# EFISSheet1.net
KiCad netlist of a schematic drawn in Altium Designer
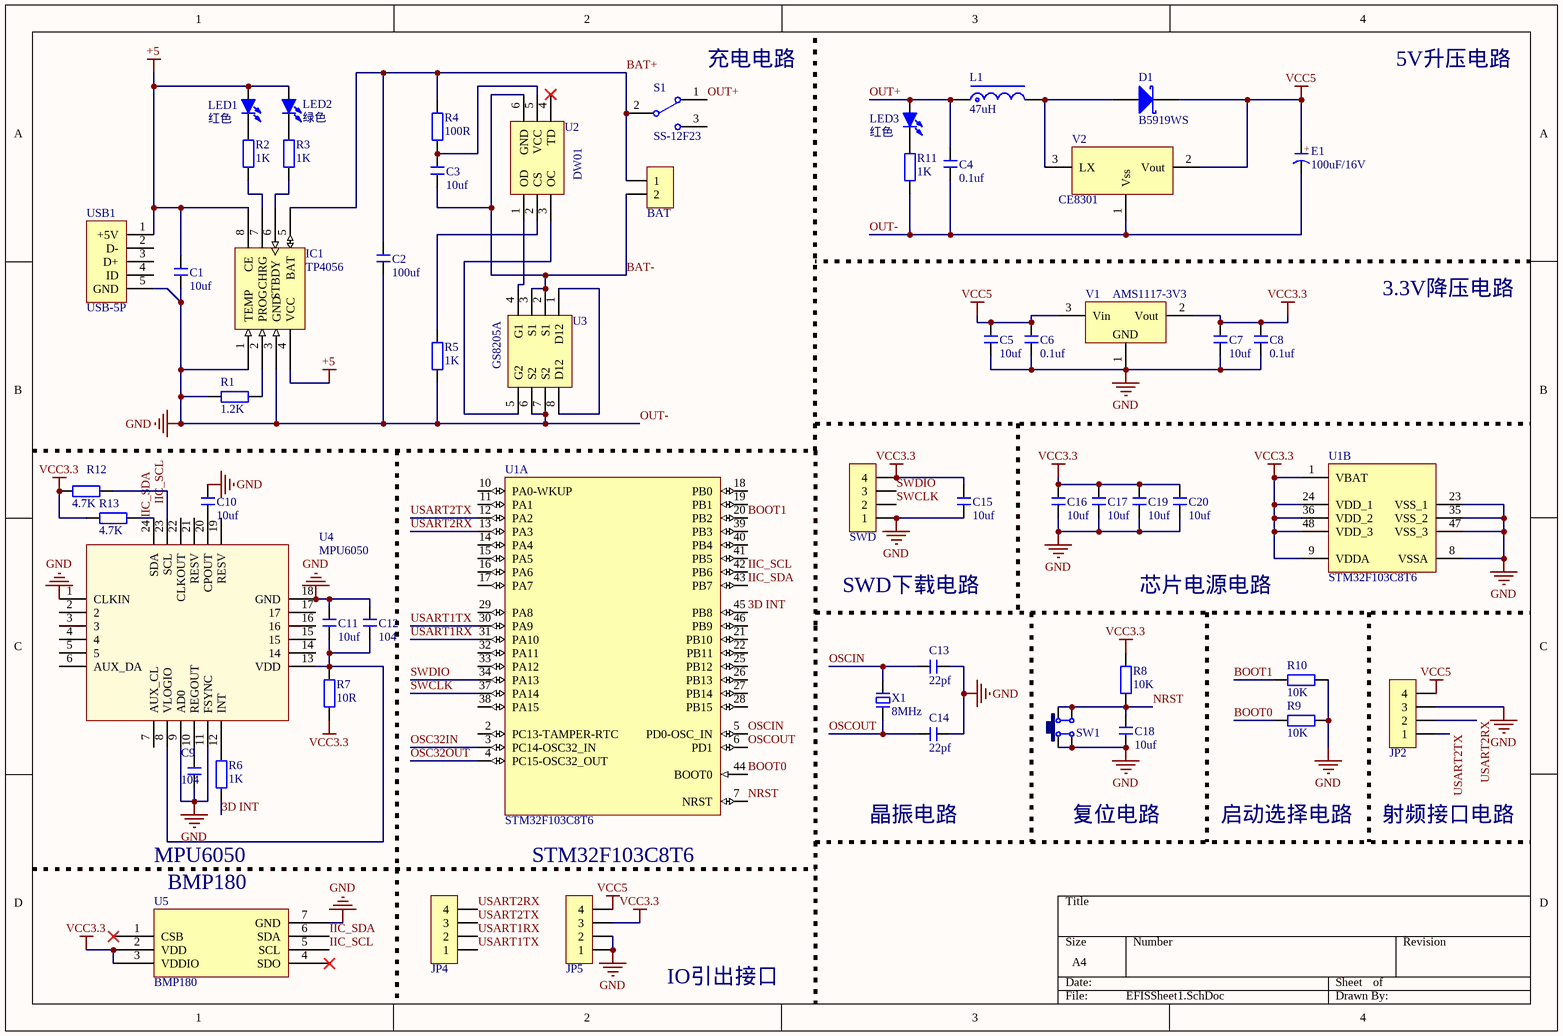
[diagram p0: EFISSheet1.SchDoc]

(export (version "E")
  (design (tool "Eeschema 10.0.6"))
  (components
    (comp (ref "BAT")
      (value "HDR-1X2")
      (footprint "XH2.54-LI-2P")
      (description "2P接插件")
      (fields (field (name "版权归属") "封装库来自淘宝 ID：黄晶宝石"))
      (libsource (lib "5.3 - 接插件-脚距2.54 (100mil) ") (part "Header 2"))
    )
    (comp (ref "C1")
      (value "10uf")
      (footprint "C 0805_L")
      (description "贴片电容")
      (libsource (lib "0.1 - 电阻-电容-电感") (part "C"))
    )
    (comp (ref "C2")
      (value "100uf")
      (footprint "C 0805_L")
      (description "贴片电容")
      (libsource (lib "0.1 - 电阻-电容-电感") (part "C"))
    )
    (comp (ref "C3")
      (value "10uf")
      (footprint "C 0805_L")
      (description "贴片电容")
      (libsource (lib "0.1 - 电阻-电容-电感") (part "C"))
    )
    (comp (ref "C4")
      (value "0.1uf")
      (footprint "C 0805_L")
      (description "贴片电容")
      (libsource (lib "0.1 - 电阻-电容-电感") (part "C"))
    )
    (comp (ref "C5")
      (value "10uf")
      (footprint "C 0805_L")
      (description "贴片电容")
      (libsource (lib "0.1 - 电阻-电容-电感") (part "C"))
    )
    (comp (ref "C6")
      (value "0.1uf")
      (footprint "C 0805_L")
      (description "贴片电容")
      (libsource (lib "0.1 - 电阻-电容-电感") (part "C"))
    )
    (comp (ref "C7")
      (value "10uf")
      (footprint "C 0805_L")
      (description "贴片电容")
      (libsource (lib "0.1 - 电阻-电容-电感") (part "C"))
    )
    (comp (ref "C8")
      (value "0.1uf")
      (footprint "C 0805_L")
      (description "贴片电容")
      (libsource (lib "0.1 - 电阻-电容-电感") (part "C"))
    )
    (comp (ref "C9")
      (value "104")
      (footprint "C 0805_L")
      (description "贴片电容")
      (libsource (lib "0.1 - 电阻-电容-电感") (part "C"))
    )
    (comp (ref "C10")
      (value "10uf")
      (footprint "C 0805_L")
      (description "贴片电容")
      (libsource (lib "0.1 - 电阻-电容-电感") (part "C"))
    )
    (comp (ref "C11")
      (value "10uf")
      (footprint "C 0805_L")
      (description "贴片电容")
      (libsource (lib "0.1 - 电阻-电容-电感") (part "C"))
    )
    (comp (ref "C12")
      (value "104")
      (footprint "C 0805_L")
      (description "贴片电容")
      (libsource (lib "0.1 - 电阻-电容-电感") (part "C"))
    )
    (comp (ref "C13")
      (value "22pf")
      (footprint "C 0805_L")
      (description "贴片电容")
      (libsource (lib "0.1 - 电阻-电容-电感") (part "C"))
    )
    (comp (ref "C14")
      (value "22pf")
      (footprint "C 0805_L")
      (description "贴片电容")
      (libsource (lib "0.1 - 电阻-电容-电感") (part "C"))
    )
    (comp (ref "C15")
      (value "10uf")
      (footprint "C 0805_L")
      (description "贴片电容")
      (libsource (lib "0.1 - 电阻-电容-电感") (part "C"))
    )
    (comp (ref "C16")
      (value "10uf")
      (footprint "C 0805_L")
      (description "贴片电容")
      (libsource (lib "0.1 - 电阻-电容-电感") (part "C"))
    )
    (comp (ref "C17")
      (value "10uf")
      (footprint "C 0805_L")
      (description "贴片电容")
      (libsource (lib "0.1 - 电阻-电容-电感") (part "C"))
    )
    (comp (ref "C18")
      (value "10uf")
      (footprint "C 0805_L")
      (description "贴片电容")
      (libsource (lib "0.1 - 电阻-电容-电感") (part "C"))
    )
    (comp (ref "C19")
      (value "10uf")
      (footprint "C 0805_L")
      (description "贴片电容")
      (libsource (lib "0.1 - 电阻-电容-电感") (part "C"))
    )
    (comp (ref "C20")
      (value "10uf")
      (footprint "C 0805_L")
      (description "贴片电容")
      (libsource (lib "0.1 - 电阻-电容-电感") (part "C"))
    )
    (comp (ref "D1")
      (value "B5919WS")
      (footprint "SOD-323")
      (description "肖特基二极管")
      (libsource (lib "0.2 -  二极管-整流桥") (part "1N5819"))
    )
    (comp (ref "E1")
      (value "100uF/16V")
      (footprint "CM D(6.3*5.4)")
      (description "贴片电解电容")
      (fields (field (name "版权归属") "封装库来自淘宝 ID：黄晶宝石"))
      (libsource (lib "0.1 - 电阻-电容-电感") (part "CE_SMD"))
    )
    (comp (ref "IC1")
      (value "TP4056")
      (footprint "SOP8_L")
      (description "外置EEPROM")
      (fields (field (name "版权归属") "封装库来自淘宝 ID：黄晶宝石"))
      (libsource (lib "1.0 - 常见芯片") (part "24Cxx"))
    )
    (comp (ref "JP2")
      (value "HDR-1X4")
      (footprint "HDR2.54-LI-4P")
      (description "4P接插件")
      (fields (field (name "版权归属") "封装库来自淘宝 ID：黄晶宝石"))
      (libsource (lib "5.3 - 接插件-脚距2.54 (100mil) ") (part "Header 4"))
    )
    (comp (ref "JP4")
      (value "HDR-1X4")
      (footprint "HDR2.54-LI-4P")
      (description "4P接插件")
      (fields (field (name "版权归属") "封装库来自淘宝 ID：黄晶宝石"))
      (libsource (lib "5.3 - 接插件-脚距2.54 (100mil) ") (part "Header 4"))
    )
    (comp (ref "JP5")
      (value "HDR-1X4")
      (footprint "HDR2.54-LI-4P")
      (description "4P接插件")
      (fields (field (name "版权归属") "封装库来自淘宝 ID：黄晶宝石"))
      (libsource (lib "5.3 - 接插件-脚距2.54 (100mil) ") (part "Header 4"))
    )
    (comp (ref "L1")
      (value "47uH")
      (footprint "CDRH73")
      (description "功率屏蔽电感")
      (fields (field (name "版权归属") "封装库来自淘宝 ID：黄晶宝石"))
      (libsource (lib "0.1 - 电阻-电容-电感") (part "L-CDRH"))
    )
    (comp (ref "LED1")
      (value "红色")
      (footprint "LED 0603R")
      (description "贴片LED")
      (fields (field (name "版权归属") "封装库来自淘宝 ID：黄晶宝石"))
      (libsource (lib "0.3 - LED发光二极管") (part "LED-SMD"))
    )
    (comp (ref "LED2")
      (value "绿色")
      (footprint "LED 0603G")
      (description "贴片LED")
      (fields (field (name "版权归属") "封装库来自淘宝 ID：黄晶宝石"))
      (libsource (lib "0.3 - LED发光二极管") (part "LED-SMD"))
    )
    (comp (ref "LED3")
      (value "红色")
      (footprint "LED 0603R")
      (description "贴片LED")
      (fields (field (name "版权归属") "封装库来自淘宝 ID：黄晶宝石"))
      (libsource (lib "0.3 - LED发光二极管") (part "LED-SMD"))
    )
    (comp (ref "R1")
      (value "1.2K")
      (footprint "R 0805_L")
      (description "贴片电阻")
      (fields (field (name "版权归属") "来自淘宝 ID：黄晶宝石"))
      (libsource (lib "0.1 - 电阻-电容-电感") (part "R"))
    )
    (comp (ref "R2")
      (value "1K")
      (footprint "R 0805_L")
      (description "贴片电阻")
      (fields (field (name "版权归属") "来自淘宝 ID：黄晶宝石"))
      (libsource (lib "0.1 - 电阻-电容-电感") (part "R"))
    )
    (comp (ref "R3")
      (value "1K")
      (footprint "R 0805_L")
      (description "贴片电阻")
      (fields (field (name "版权归属") "来自淘宝 ID：黄晶宝石"))
      (libsource (lib "0.1 - 电阻-电容-电感") (part "R"))
    )
    (comp (ref "R4")
      (value "100R")
      (footprint "R 0805_L")
      (description "贴片电阻")
      (fields (field (name "版权归属") "来自淘宝 ID：黄晶宝石"))
      (libsource (lib "0.1 - 电阻-电容-电感") (part "R"))
    )
    (comp (ref "R5")
      (value "1K")
      (footprint "R 0805_L")
      (description "贴片电阻")
      (fields (field (name "版权归属") "来自淘宝 ID：黄晶宝石"))
      (libsource (lib "0.1 - 电阻-电容-电感") (part "R"))
    )
    (comp (ref "R6")
      (value "1K")
      (footprint "R 0805_L")
      (description "贴片电阻")
      (fields (field (name "版权归属") "来自淘宝 ID：黄晶宝石"))
      (libsource (lib "0.1 - 电阻-电容-电感") (part "R"))
    )
    (comp (ref "R7")
      (value "10R")
      (footprint "R 0805_L")
      (description "贴片电阻")
      (fields (field (name "版权归属") "来自淘宝 ID：黄晶宝石"))
      (libsource (lib "0.1 - 电阻-电容-电感") (part "R"))
    )
    (comp (ref "R8")
      (value "10K")
      (footprint "R 0805_L")
      (description "贴片电阻")
      (fields (field (name "版权归属") "来自淘宝 ID：黄晶宝石"))
      (libsource (lib "0.1 - 电阻-电容-电感") (part "R"))
    )
    (comp (ref "R9")
      (value "10K")
      (footprint "R 0805_L")
      (description "贴片电阻")
      (fields (field (name "版权归属") "来自淘宝 ID：黄晶宝石"))
      (libsource (lib "0.1 - 电阻-电容-电感") (part "R"))
    )
    (comp (ref "R10")
      (value "10K")
      (footprint "R 0805_L")
      (description "贴片电阻")
      (fields (field (name "版权归属") "来自淘宝 ID：黄晶宝石"))
      (libsource (lib "0.1 - 电阻-电容-电感") (part "R"))
    )
    (comp (ref "R11")
      (value "1K")
      (footprint "R 0805_L")
      (description "贴片电阻")
      (fields (field (name "版权归属") "来自淘宝 ID：黄晶宝石"))
      (libsource (lib "0.1 - 电阻-电容-电感") (part "R"))
    )
    (comp (ref "R12")
      (value "4.7K")
      (footprint "R 0805_L")
      (description "贴片电阻")
      (fields (field (name "版权归属") "来自淘宝 ID：黄晶宝石"))
      (libsource (lib "0.1 - 电阻-电容-电感") (part "R"))
    )
    (comp (ref "R13")
      (value "4.7K")
      (footprint "R 0805_L")
      (description "贴片电阻")
      (fields (field (name "版权归属") "来自淘宝 ID：黄晶宝石"))
      (libsource (lib "0.1 - 电阻-电容-电感") (part "R"))
    )
    (comp (ref "S1")
      (value "SS-12F23")
      (footprint "MSK-12C01-07")
      (description "1路波动开关")
      (fields (field (name "版权归属") "封装库来自淘宝 ID：黄晶宝石"))
      (libsource (lib "0.7 - 常用按键-开关") (part "SSW-1P"))
    )
    (comp (ref "SW1")
      (value "6x6x5")
      (footprint "TSW SMD-6*6*5")
      (description "贴片6x6轻触开关")
      (fields (field (name "版权归属") "封装库来自淘宝 ID：黄晶宝石"))
      (libsource (lib "0.7 - 常用按键-开关") (part "TSW SMD-6x6"))
    )
    (comp (ref "SWD")
      (value "HDR-1X4")
      (footprint "HDR2.54-LI-4P")
      (description "4P接插件")
      (fields (field (name "版权归属") "封装库来自淘宝 ID：黄晶宝石"))
      (libsource (lib "5.3 - 接插件-脚距2.54 (100mil) ") (part "Header 4"))
    )
    (comp (ref "U1")
      (value "STM32F103C8T6")
      (footprint "LQFP48_N")
      (libsource (lib "2.3 - STM32 F1系列MCU 集成库") (part "STM32F103C8T6"))
    )
    (comp (ref "U2")
      (value "DW01")
      (footprint "SOT23-6N")
      (description "锂电池过流保护IC")
      (libsource (lib "1.1 - 电源类芯片") (part "DW01"))
    )
    (comp (ref "U3")
      (value "GS8205A")
      (footprint "SSOP8_N")
      (description "N沟道增强型功率场效应管")
      (fields (field (name "版权归属") "源创客"))
      (libsource (lib "0.5 - 场效应管-可控硅") (part "GS8205A"))
    )
    (comp (ref "U4")
      (value "MPU6050")
      (footprint "QFN_24")
      (description "三轴加速度+三轴陀螺仪")
      (libsource (lib "1.0 - 常见芯片") (part "MPU6050"))
    )
    (comp (ref "U5") (value "BMP180") (footprint "LGA7") (libsource (lib "Schlib1") (part "BMP180")))
    (comp (ref "USB1")
      (value "USB-5P")
      (footprint "USB-MICRO_A")
      (description "微型USB母座")
      (libsource (lib "0.8 - 以太网-音频-USB插座") (part "USB-5P"))
    )
    (comp (ref "V1")
      (value "AMS1117-3V3")
      (footprint "SOT223_N")
      (description "三端稳压芯片")
      (libsource (lib "1.1 - 电源类芯片") (part "AMS1117"))
    )
    (comp (ref "V2")
      (value "CE8301")
      (footprint "SOT89_N")
      (description "LDO线性稳压芯片")
      (fields (field (name "版权归属") "封装库来自淘宝 ID：黄晶宝石"))
      (libsource (lib "1.1 - 电源类芯片") (part "HT71xx"))
    )
    (comp (ref "X1")
      (value "8MHz")
      (footprint "OSC HC-49SMD")
      (description "2脚无源脚晶振")
      (fields (field (name "版权归属") "封装库来自淘宝卖家 ID：黄晶宝石"))
      (libsource (lib "2.0 - 保险丝-晶振-光耦") (part "XTAL-2P"))
    )
  )
  (nets
    (net (code "1") (name "+5") (class "Default")
      (node (ref "C1") (pin "2") (pinfunction "2_2") (pintype "passive"))
      (node (ref "IC1") (pin "4") (pinfunction "VCC_4") (pintype "passive"))
      (node (ref "IC1") (pin "8") (pinfunction "CE_8") (pintype "power_in"))
      (node (ref "LED1") (pin "1") (pinfunction "A_1") (pintype "passive"))
      (node (ref "LED2") (pin "1") (pinfunction "A_1") (pintype "passive"))
      (node (ref "USB1") (pin "1") (pinfunction "+5V_1") (pintype "passive"))
    )
    (net (code "2") (name "/3D INT") (class "Default")
      (node (ref "R6") (pin "2") (pinfunction "2_2") (pintype "passive"))
      (node (ref "U1") (pin "45") (pinfunction "PB8_45") (pintype "bidirectional"))
    )
    (net (code "3") (name "/BAT+") (class "Default")
      (node (ref "BAT") (pin "1") (pinfunction "1_1") (pintype "passive"))
      (node (ref "C2") (pin "2") (pinfunction "2_2") (pintype "passive"))
      (node (ref "IC1") (pin "5") (pinfunction "BAT_5") (pintype "bidirectional"))
      (node (ref "R4") (pin "2") (pinfunction "2_2") (pintype "passive"))
      (node (ref "S1") (pin "2") (pinfunction "2_2") (pintype "passive"))
    )
    (net (code "4") (name "/BAT-") (class "Default")
      (node (ref "BAT") (pin "2") (pinfunction "2_2") (pintype "passive"))
      (node (ref "C3") (pin "1") (pinfunction "1_1") (pintype "passive"))
      (node (ref "U2") (pin "6") (pinfunction "GND_6") (pintype "passive"))
      (node (ref "U3") (pin "2") (pinfunction "S1_2") (pintype "passive"))
      (node (ref "U3") (pin "3") (pinfunction "S1_3") (pintype "passive"))
    )
    (net (code "5") (name "/BOOT0") (class "Default")
      (node (ref "R9") (pin "2") (pinfunction "2_2") (pintype "passive"))
      (node (ref "U1") (pin "44") (pinfunction "BOOT0_44") (pintype "input"))
    )
    (net (code "6") (name "/BOOT1") (class "Default")
      (node (ref "R10") (pin "1") (pinfunction "1_1") (pintype "passive"))
      (node (ref "U1") (pin "20") (pinfunction "PB2_20") (pintype "bidirectional"))
    )
    (net (code "7") (name "/IIC_SCL") (class "Default")
      (node (ref "R12") (pin "2") (pinfunction "2_2") (pintype "passive"))
      (node (ref "U1") (pin "42") (pinfunction "PB6_42") (pintype "bidirectional"))
      (node (ref "U4") (pin "23") (pinfunction "SCL_23") (pintype "passive"))
      (node (ref "U5") (pin "5") (pinfunction "SCL_5") (pintype "passive"))
    )
    (net (code "8") (name "/IIC_SDA") (class "Default")
      (node (ref "R13") (pin "2") (pinfunction "2_2") (pintype "passive"))
      (node (ref "U1") (pin "43") (pinfunction "PB7_43") (pintype "bidirectional"))
      (node (ref "U4") (pin "24") (pinfunction "SDA_24") (pintype "passive"))
      (node (ref "U5") (pin "6") (pinfunction "SDA_6") (pintype "passive"))
    )
    (net (code "9") (name "/NRST") (class "Default")
      (node (ref "C18") (pin "2") (pinfunction "2_2") (pintype "passive"))
      (node (ref "R8") (pin "2") (pinfunction "2_2") (pintype "passive"))
      (node (ref "SW1") (pin "2") (pinfunction "2_2") (pintype "passive"))
      (node (ref "SW1") (pin "3") (pinfunction "3_3") (pintype "passive"))
      (node (ref "U1") (pin "7") (pinfunction "NRST_7") (pintype "bidirectional"))
    )
    (net (code "10") (name "/OSC32IN") (class "Default")
      (node (ref "U1") (pin "3") (pinfunction "PC14-OSC32_IN_3") (pintype "bidirectional"))
    )
    (net (code "11") (name "/OSC32OUT") (class "Default")
      (node (ref "U1") (pin "4") (pinfunction "PC15-OSC32_OUT_4") (pintype "bidirectional"))
    )
    (net (code "12") (name "/OSCIN") (class "Default")
      (node (ref "C13") (pin "2") (pinfunction "2_2") (pintype "passive"))
      (node (ref "U1") (pin "5") (pinfunction "PD0-OSC_IN_5") (pintype "bidirectional"))
      (node (ref "X1") (pin "2") (pinfunction "2_2") (pintype "passive"))
    )
    (net (code "13") (name "/OSCOUT") (class "Default")
      (node (ref "C14") (pin "2") (pinfunction "2_2") (pintype "passive"))
      (node (ref "U1") (pin "6") (pinfunction "PD1_6") (pintype "bidirectional"))
      (node (ref "X1") (pin "1") (pinfunction "1_1") (pintype "passive"))
    )
    (net (code "14") (name "/OUT+") (class "Default")
      (node (ref "C4") (pin "2") (pinfunction "2_2") (pintype "passive"))
      (node (ref "L1") (pin "1") (pinfunction "1_1") (pintype "passive"))
      (node (ref "LED3") (pin "1") (pinfunction "A_1") (pintype "passive"))
      (node (ref "S1") (pin "1") (pinfunction "1_1") (pintype "passive"))
    )
    (net (code "15") (name "/SWCLK") (class "Default")
      (node (ref "SWD") (pin "2") (pinfunction "2_2") (pintype "passive"))
      (node (ref "U1") (pin "37") (pinfunction "PA14_37") (pintype "bidirectional"))
    )
    (net (code "16") (name "/SWDIO") (class "Default")
      (node (ref "SWD") (pin "3") (pinfunction "3_3") (pintype "passive"))
      (node (ref "U1") (pin "34") (pinfunction "PA13_34") (pintype "bidirectional"))
    )
    (net (code "17") (name "/USART1RX") (class "Default")
      (node (ref "JP4") (pin "2") (pinfunction "2_2") (pintype "passive"))
      (node (ref "U1") (pin "31") (pinfunction "PA10_31") (pintype "bidirectional"))
    )
    (net (code "18") (name "/USART1TX") (class "Default")
      (node (ref "JP4") (pin "1") (pinfunction "1_1") (pintype "passive"))
      (node (ref "U1") (pin "30") (pinfunction "PA9_30") (pintype "bidirectional"))
    )
    (net (code "19") (name "/USART2RX") (class "Default")
      (node (ref "JP2") (pin "2") (pinfunction "2_2") (pintype "passive"))
      (node (ref "JP4") (pin "4") (pinfunction "4_4") (pintype "passive"))
      (node (ref "U1") (pin "13") (pinfunction "PA3_13") (pintype "bidirectional"))
    )
    (net (code "20") (name "/USART2TX") (class "Default")
      (node (ref "JP2") (pin "1") (pinfunction "1_1") (pintype "passive"))
      (node (ref "JP4") (pin "3") (pinfunction "3_3") (pintype "passive"))
      (node (ref "U1") (pin "12") (pinfunction "PA2_12") (pintype "bidirectional"))
    )
    (net (code "21") (name "GND") (class "Default")
      (node (ref "C1") (pin "1") (pinfunction "1_1") (pintype "passive"))
      (node (ref "C10") (pin "2") (pinfunction "2_2") (pintype "passive"))
      (node (ref "C11") (pin "2") (pinfunction "2_2") (pintype "passive"))
      (node (ref "C12") (pin "2") (pinfunction "2_2") (pintype "passive"))
      (node (ref "C13") (pin "1") (pinfunction "1_1") (pintype "passive"))
      (node (ref "C14") (pin "1") (pinfunction "1_1") (pintype "passive"))
      (node (ref "C15") (pin "1") (pinfunction "1_1") (pintype "passive"))
      (node (ref "C16") (pin "1") (pinfunction "1_1") (pintype "passive"))
      (node (ref "C17") (pin "1") (pinfunction "1_1") (pintype "passive"))
      (node (ref "C18") (pin "1") (pinfunction "1_1") (pintype "passive"))
      (node (ref "C19") (pin "1") (pinfunction "1_1") (pintype "passive"))
      (node (ref "C2") (pin "1") (pinfunction "1_1") (pintype "passive"))
      (node (ref "C20") (pin "1") (pinfunction "1_1") (pintype "passive"))
      (node (ref "C4") (pin "1") (pinfunction "1_1") (pintype "passive"))
      (node (ref "C5") (pin "1") (pinfunction "1_1") (pintype "passive"))
      (node (ref "C6") (pin "1") (pinfunction "1_1") (pintype "passive"))
      (node (ref "C7") (pin "1") (pinfunction "1_1") (pintype "passive"))
      (node (ref "C8") (pin "1") (pinfunction "1_1") (pintype "passive"))
      (node (ref "C9") (pin "1") (pinfunction "1_1") (pintype "passive"))
      (node (ref "E1") (pin "2") (pinfunction "K_2") (pintype "passive"))
      (node (ref "IC1") (pin "1") (pinfunction "TEMP_1") (pintype "input"))
      (node (ref "IC1") (pin "3") (pinfunction "GND_3") (pintype "input"))
      (node (ref "JP2") (pin "3") (pinfunction "3_3") (pintype "passive"))
      (node (ref "JP5") (pin "1") (pinfunction "1_1") (pintype "passive"))
      (node (ref "JP5") (pin "2") (pinfunction "2_2") (pintype "passive"))
      (node (ref "R1") (pin "1") (pinfunction "1_1") (pintype "passive"))
      (node (ref "R10") (pin "2") (pinfunction "2_2") (pintype "passive"))
      (node (ref "R11") (pin "2") (pinfunction "2_2") (pintype "passive"))
      (node (ref "R5") (pin "1") (pinfunction "1_1") (pintype "passive"))
      (node (ref "R9") (pin "1") (pinfunction "1_1") (pintype "passive"))
      (node (ref "SW1") (pin "1") (pinfunction "1_1") (pintype "passive"))
      (node (ref "SW1") (pin "4") (pinfunction "4_4") (pintype "passive"))
      (node (ref "SWD") (pin "1") (pinfunction "1_1") (pintype "passive"))
      (node (ref "U1") (pin "23") (pinfunction "VSS_1_23") (pintype "power_in"))
      (node (ref "U1") (pin "35") (pinfunction "VSS_2_35") (pintype "power_in"))
      (node (ref "U1") (pin "47") (pinfunction "VSS_3_47") (pintype "power_in"))
      (node (ref "U1") (pin "8") (pinfunction "VSSA_8") (pintype "power_in"))
      (node (ref "U3") (pin "6") (pinfunction "S2_6") (pintype "passive"))
      (node (ref "U3") (pin "7") (pinfunction "S2_7") (pintype "passive"))
      (node (ref "U4") (pin "1") (pinfunction "CLKIN_1") (pintype "passive"))
      (node (ref "U4") (pin "11") (pinfunction "FSYNC_11") (pintype "passive"))
      (node (ref "U4") (pin "18") (pinfunction "GND_18") (pintype "passive"))
      (node (ref "U4") (pin "9") (pinfunction "AD0_9") (pintype "passive"))
      (node (ref "U5") (pin "7") (pinfunction "GND_7") (pintype "passive"))
      (node (ref "USB1") (pin "5") (pinfunction "GND_5") (pintype "passive"))
      (node (ref "V1") (pin "1") (pinfunction "GND_1") (pintype "passive"))
      (node (ref "V2") (pin "1") (pinfunction "Vss_1") (pintype "passive"))
    )
    (net (code "22") (name "Net-(D1-A)") (class "Default")
      (node (ref "D1") (pin "1") (pinfunction "A_1") (pintype "passive"))
      (node (ref "L1") (pin "2") (pinfunction "2_2") (pintype "passive"))
      (node (ref "V2") (pin "3") (pinfunction "LX_3") (pintype "passive"))
    )
    (net (code "23") (name "Net-(IC1-CHRG)") (class "Default")
      (node (ref "IC1") (pin "7") (pinfunction "CHRG_7") (pintype "passive"))
      (node (ref "R2") (pin "2") (pinfunction "2_2") (pintype "passive"))
    )
    (net (code "24") (name "Net-(IC1-PROG)") (class "Default")
      (node (ref "IC1") (pin "2") (pinfunction "PROG_2") (pintype "input"))
      (node (ref "R1") (pin "2") (pinfunction "2_2") (pintype "passive"))
    )
    (net (code "25") (name "Net-(IC1-STBDY)") (class "Default")
      (node (ref "IC1") (pin "6") (pinfunction "STBDY_6") (pintype "input"))
      (node (ref "R3") (pin "1") (pinfunction "1_1") (pintype "passive"))
    )
    (net (code "26") (name "Net-(LED1-K)") (class "Default")
      (node (ref "LED1") (pin "2") (pinfunction "K_2") (pintype "passive"))
      (node (ref "R2") (pin "1") (pinfunction "1_1") (pintype "passive"))
    )
    (net (code "27") (name "Net-(LED2-K)") (class "Default")
      (node (ref "LED2") (pin "2") (pinfunction "K_2") (pintype "passive"))
      (node (ref "R3") (pin "2") (pinfunction "2_2") (pintype "passive"))
    )
    (net (code "28") (name "Net-(LED3-K)") (class "Default")
      (node (ref "LED3") (pin "2") (pinfunction "K_2") (pintype "passive"))
      (node (ref "R11") (pin "1") (pinfunction "1_1") (pintype "passive"))
    )
    (net (code "29") (name "Net-(U2-CS)") (class "Default")
      (node (ref "R5") (pin "2") (pinfunction "2_2") (pintype "passive"))
      (node (ref "U2") (pin "2") (pinfunction "CS_2") (pintype "passive"))
    )
    (net (code "30") (name "Net-(U2-OC)") (class "Default")
      (node (ref "U2") (pin "3") (pinfunction "OC_3") (pintype "passive"))
      (node (ref "U3") (pin "5") (pinfunction "G2_5") (pintype "passive"))
    )
    (net (code "31") (name "Net-(U2-OD)") (class "Default")
      (node (ref "U2") (pin "1") (pinfunction "OD_1") (pintype "passive"))
      (node (ref "U3") (pin "4") (pinfunction "G1_4") (pintype "passive"))
    )
    (net (code "32") (name "Net-(U2-VCC)") (class "Default")
      (node (ref "C3") (pin "2") (pinfunction "2_2") (pintype "passive"))
      (node (ref "R4") (pin "1") (pinfunction "1_1") (pintype "passive"))
      (node (ref "U2") (pin "5") (pinfunction "VCC_5") (pintype "passive"))
    )
    (net (code "33") (name "Net-(U3-D12-Pad1)") (class "Default")
      (node (ref "U3") (pin "1") (pinfunction "D12_1") (pintype "passive"))
      (node (ref "U3") (pin "8") (pinfunction "D12_8") (pintype "passive"))
    )
    (net (code "34") (name "Net-(U4-CPOUT)") (class "Default")
      (node (ref "C10") (pin "1") (pinfunction "1_1") (pintype "passive"))
      (node (ref "U4") (pin "20") (pinfunction "CPOUT_20") (pintype "passive"))
    )
    (net (code "35") (name "Net-(U4-INT)") (class "Default")
      (node (ref "R6") (pin "1") (pinfunction "1_1") (pintype "passive"))
      (node (ref "U4") (pin "12") (pinfunction "INT_12") (pintype "passive"))
    )
    (net (code "36") (name "Net-(U4-REGOUT)") (class "Default")
      (node (ref "C9") (pin "2") (pinfunction "2_2") (pintype "passive"))
      (node (ref "U4") (pin "10") (pinfunction "REGOUT_10") (pintype "passive"))
    )
    (net (code "37") (name "Net-(U4-VDD)") (class "Default")
      (node (ref "C11") (pin "1") (pinfunction "1_1") (pintype "passive"))
      (node (ref "C12") (pin "1") (pinfunction "1_1") (pintype "passive"))
      (node (ref "R7") (pin "2") (pinfunction "2_2") (pintype "passive"))
      (node (ref "U4") (pin "13") (pinfunction "VDD_13") (pintype "passive"))
      (node (ref "U4") (pin "8") (pinfunction "VLOGIO_8") (pintype "passive"))
    )
    (net (code "38") (name "VCC3.3") (class "Default")
      (node (ref "C15") (pin "2") (pinfunction "2_2") (pintype "passive"))
      (node (ref "C16") (pin "2") (pinfunction "2_2") (pintype "passive"))
      (node (ref "C17") (pin "2") (pinfunction "2_2") (pintype "passive"))
      (node (ref "C19") (pin "2") (pinfunction "2_2") (pintype "passive"))
      (node (ref "C20") (pin "2") (pinfunction "2_2") (pintype "passive"))
      (node (ref "C7") (pin "2") (pinfunction "2_2") (pintype "passive"))
      (node (ref "C8") (pin "2") (pinfunction "2_2") (pintype "passive"))
      (node (ref "JP5") (pin "3") (pinfunction "3_3") (pintype "passive"))
      (node (ref "R12") (pin "1") (pinfunction "1_1") (pintype "passive"))
      (node (ref "R13") (pin "1") (pinfunction "1_1") (pintype "passive"))
      (node (ref "R7") (pin "1") (pinfunction "1_1") (pintype "passive"))
      (node (ref "R8") (pin "1") (pinfunction "1_1") (pintype "passive"))
      (node (ref "SWD") (pin "4") (pinfunction "4_4") (pintype "passive"))
      (node (ref "U1") (pin "1") (pinfunction "VBAT_1") (pintype "power_in"))
      (node (ref "U1") (pin "24") (pinfunction "VDD_1_24") (pintype "power_in"))
      (node (ref "U1") (pin "36") (pinfunction "VDD_2_36") (pintype "power_in"))
      (node (ref "U1") (pin "48") (pinfunction "VDD_3_48") (pintype "power_in"))
      (node (ref "U1") (pin "9") (pinfunction "VDDA_9") (pintype "power_in"))
      (node (ref "U5") (pin "2") (pinfunction "VDD_2") (pintype "passive"))
      (node (ref "U5") (pin "3") (pinfunction "VDDIO_3") (pintype "passive"))
      (node (ref "V1") (pin "2") (pinfunction "Vout_2") (pintype "passive"))
    )
    (net (code "39") (name "VCC5") (class "Default")
      (node (ref "C5") (pin "2") (pinfunction "2_2") (pintype "passive"))
      (node (ref "C6") (pin "2") (pinfunction "2_2") (pintype "passive"))
      (node (ref "D1") (pin "2") (pinfunction "K_2") (pintype "passive"))
      (node (ref "E1") (pin "1") (pinfunction "A_1") (pintype "passive"))
      (node (ref "JP2") (pin "4") (pinfunction "4_4") (pintype "passive"))
      (node (ref "JP5") (pin "4") (pinfunction "4_4") (pintype "passive"))
      (node (ref "V1") (pin "3") (pinfunction "Vin_3") (pintype "passive"))
      (node (ref "V2") (pin "2") (pinfunction "Vout_2") (pintype "passive"))
    )
    (net (code "40") (name "unconnected-(S1-Pad3)") (class "Default")
      (node (ref "S1") (pin "3") (pinfunction "3_3") (pintype "passive"))
    )
    (net (code "41") (name "unconnected-(U1A-PA0-WKUP-Pad10)") (class "Default")
      (node (ref "U1") (pin "10") (pinfunction "PA0-WKUP_10") (pintype "bidirectional"))
    )
    (net (code "42") (name "unconnected-(U1A-PA1-Pad11)") (class "Default")
      (node (ref "U1") (pin "11") (pinfunction "PA1_11") (pintype "bidirectional"))
    )
    (net (code "43") (name "unconnected-(U1A-PA4-Pad14)") (class "Default")
      (node (ref "U1") (pin "14") (pinfunction "PA4_14") (pintype "bidirectional"))
    )
    (net (code "44") (name "unconnected-(U1A-PA5-Pad15)") (class "Default")
      (node (ref "U1") (pin "15") (pinfunction "PA5_15") (pintype "bidirectional"))
    )
    (net (code "45") (name "unconnected-(U1A-PA6-Pad16)") (class "Default")
      (node (ref "U1") (pin "16") (pinfunction "PA6_16") (pintype "bidirectional"))
    )
    (net (code "46") (name "unconnected-(U1A-PA7-Pad17)") (class "Default")
      (node (ref "U1") (pin "17") (pinfunction "PA7_17") (pintype "bidirectional"))
    )
    (net (code "47") (name "unconnected-(U1A-PA8-Pad29)") (class "Default")
      (node (ref "U1") (pin "29") (pinfunction "PA8_29") (pintype "bidirectional"))
    )
    (net (code "48") (name "unconnected-(U1A-PA11-Pad32)") (class "Default")
      (node (ref "U1") (pin "32") (pinfunction "PA11_32") (pintype "bidirectional"))
    )
    (net (code "49") (name "unconnected-(U1A-PA12-Pad33)") (class "Default")
      (node (ref "U1") (pin "33") (pinfunction "PA12_33") (pintype "bidirectional"))
    )
    (net (code "50") (name "unconnected-(U1A-PA15-Pad38)") (class "Default")
      (node (ref "U1") (pin "38") (pinfunction "PA15_38") (pintype "bidirectional"))
    )
    (net (code "51") (name "unconnected-(U1A-PB0-Pad18)") (class "Default")
      (node (ref "U1") (pin "18") (pinfunction "PB0_18") (pintype "bidirectional"))
    )
    (net (code "52") (name "unconnected-(U1A-PB1-Pad19)") (class "Default")
      (node (ref "U1") (pin "19") (pinfunction "PB1_19") (pintype "bidirectional"))
    )
    (net (code "53") (name "unconnected-(U1A-PB3-Pad39)") (class "Default")
      (node (ref "U1") (pin "39") (pinfunction "PB3_39") (pintype "bidirectional"))
    )
    (net (code "54") (name "unconnected-(U1A-PB4-Pad40)") (class "Default")
      (node (ref "U1") (pin "40") (pinfunction "PB4_40") (pintype "bidirectional"))
    )
    (net (code "55") (name "unconnected-(U1A-PB5-Pad41)") (class "Default")
      (node (ref "U1") (pin "41") (pinfunction "PB5_41") (pintype "bidirectional"))
    )
    (net (code "56") (name "unconnected-(U1A-PB9-Pad46)") (class "Default")
      (node (ref "U1") (pin "46") (pinfunction "PB9_46") (pintype "bidirectional"))
    )
    (net (code "57") (name "unconnected-(U1A-PB10-Pad21)") (class "Default")
      (node (ref "U1") (pin "21") (pinfunction "PB10_21") (pintype "bidirectional"))
    )
    (net (code "58") (name "unconnected-(U1A-PB11-Pad22)") (class "Default")
      (node (ref "U1") (pin "22") (pinfunction "PB11_22") (pintype "bidirectional"))
    )
    (net (code "59") (name "unconnected-(U1A-PB12-Pad25)") (class "Default")
      (node (ref "U1") (pin "25") (pinfunction "PB12_25") (pintype "bidirectional"))
    )
    (net (code "60") (name "unconnected-(U1A-PB13-Pad26)") (class "Default")
      (node (ref "U1") (pin "26") (pinfunction "PB13_26") (pintype "bidirectional"))
    )
    (net (code "61") (name "unconnected-(U1A-PB14-Pad27)") (class "Default")
      (node (ref "U1") (pin "27") (pinfunction "PB14_27") (pintype "bidirectional"))
    )
    (net (code "62") (name "unconnected-(U1A-PB15-Pad28)") (class "Default")
      (node (ref "U1") (pin "28") (pinfunction "PB15_28") (pintype "bidirectional"))
    )
    (net (code "63") (name "unconnected-(U1A-PC13-TAMPER-RTC-Pad2)") (class "Default")
      (node (ref "U1") (pin "2") (pinfunction "PC13-TAMPER-RTC_2") (pintype "bidirectional"))
    )
    (net (code "64") (name "unconnected-(U2-TD-Pad4)") (class "Default")
      (node (ref "U2") (pin "4") (pinfunction "TD_4") (pintype "passive+no_connect"))
    )
    (net (code "65") (name "unconnected-(U4-AUX_CL-Pad7)") (class "Default")
      (node (ref "U4") (pin "7") (pinfunction "AUX_CL_7") (pintype "passive"))
    )
    (net (code "66") (name "unconnected-(U4-AUX_DA-Pad6)") (class "Default")
      (node (ref "U4") (pin "6") (pinfunction "AUX_DA_6") (pintype "passive"))
    )
    (net (code "67") (name "unconnected-(U4-CLKOUT-Pad22)") (class "Default")
      (node (ref "U4") (pin "22") (pinfunction "CLKOUT_22") (pintype "passive"))
    )
    (net (code "68") (name "unconnected-(U4-Pad2)") (class "Default")
      (node (ref "U4") (pin "2") (pinfunction "2_2") (pintype "passive"))
    )
    (net (code "69") (name "unconnected-(U4-Pad3)") (class "Default")
      (node (ref "U4") (pin "3") (pinfunction "3_3") (pintype "passive"))
    )
    (net (code "70") (name "unconnected-(U4-Pad4)") (class "Default")
      (node (ref "U4") (pin "4") (pinfunction "4_4") (pintype "passive"))
    )
    (net (code "71") (name "unconnected-(U4-Pad5)") (class "Default")
      (node (ref "U4") (pin "5") (pinfunction "5_5") (pintype "passive"))
    )
    (net (code "72") (name "unconnected-(U4-Pad14)") (class "Default")
      (node (ref "U4") (pin "14") (pinfunction "14_14") (pintype "passive"))
    )
    (net (code "73") (name "unconnected-(U4-Pad15)") (class "Default")
      (node (ref "U4") (pin "15") (pinfunction "15_15") (pintype "passive"))
    )
    (net (code "74") (name "unconnected-(U4-Pad16)") (class "Default")
      (node (ref "U4") (pin "16") (pinfunction "16_16") (pintype "passive"))
    )
    (net (code "75") (name "unconnected-(U4-Pad17)") (class "Default")
      (node (ref "U4") (pin "17") (pinfunction "17_17") (pintype "passive"))
    )
    (net (code "76") (name "unconnected-(U4-RESV-Pad19)") (class "Default")
      (node (ref "U4") (pin "19") (pinfunction "RESV_19") (pintype "passive"))
    )
    (net (code "77") (name "unconnected-(U4-RESV-Pad21)") (class "Default")
      (node (ref "U4") (pin "21") (pinfunction "RESV_21") (pintype "passive"))
    )
    (net (code "78") (name "unconnected-(U5-CSB-Pad1)") (class "Default")
      (node (ref "U5") (pin "1") (pinfunction "CSB_1") (pintype "passive+no_connect"))
    )
    (net (code "79") (name "unconnected-(U5-SDO-Pad4)") (class "Default")
      (node (ref "U5") (pin "4") (pinfunction "SDO_4") (pintype "passive+no_connect"))
    )
    (net (code "80") (name "unconnected-(USB1-D+-Pad3)") (class "Default")
      (node (ref "USB1") (pin "3") (pinfunction "D+_3") (pintype "passive"))
    )
    (net (code "81") (name "unconnected-(USB1-D--Pad2)") (class "Default")
      (node (ref "USB1") (pin "2") (pinfunction "D-_2") (pintype "passive"))
    )
    (net (code "82") (name "unconnected-(USB1-ID-Pad4)") (class "Default")
      (node (ref "USB1") (pin "4") (pinfunction "ID_4") (pintype "passive"))
    )
  )
)
